# utorch.net
KiCad netlist of a schematic drawn in EAGLE
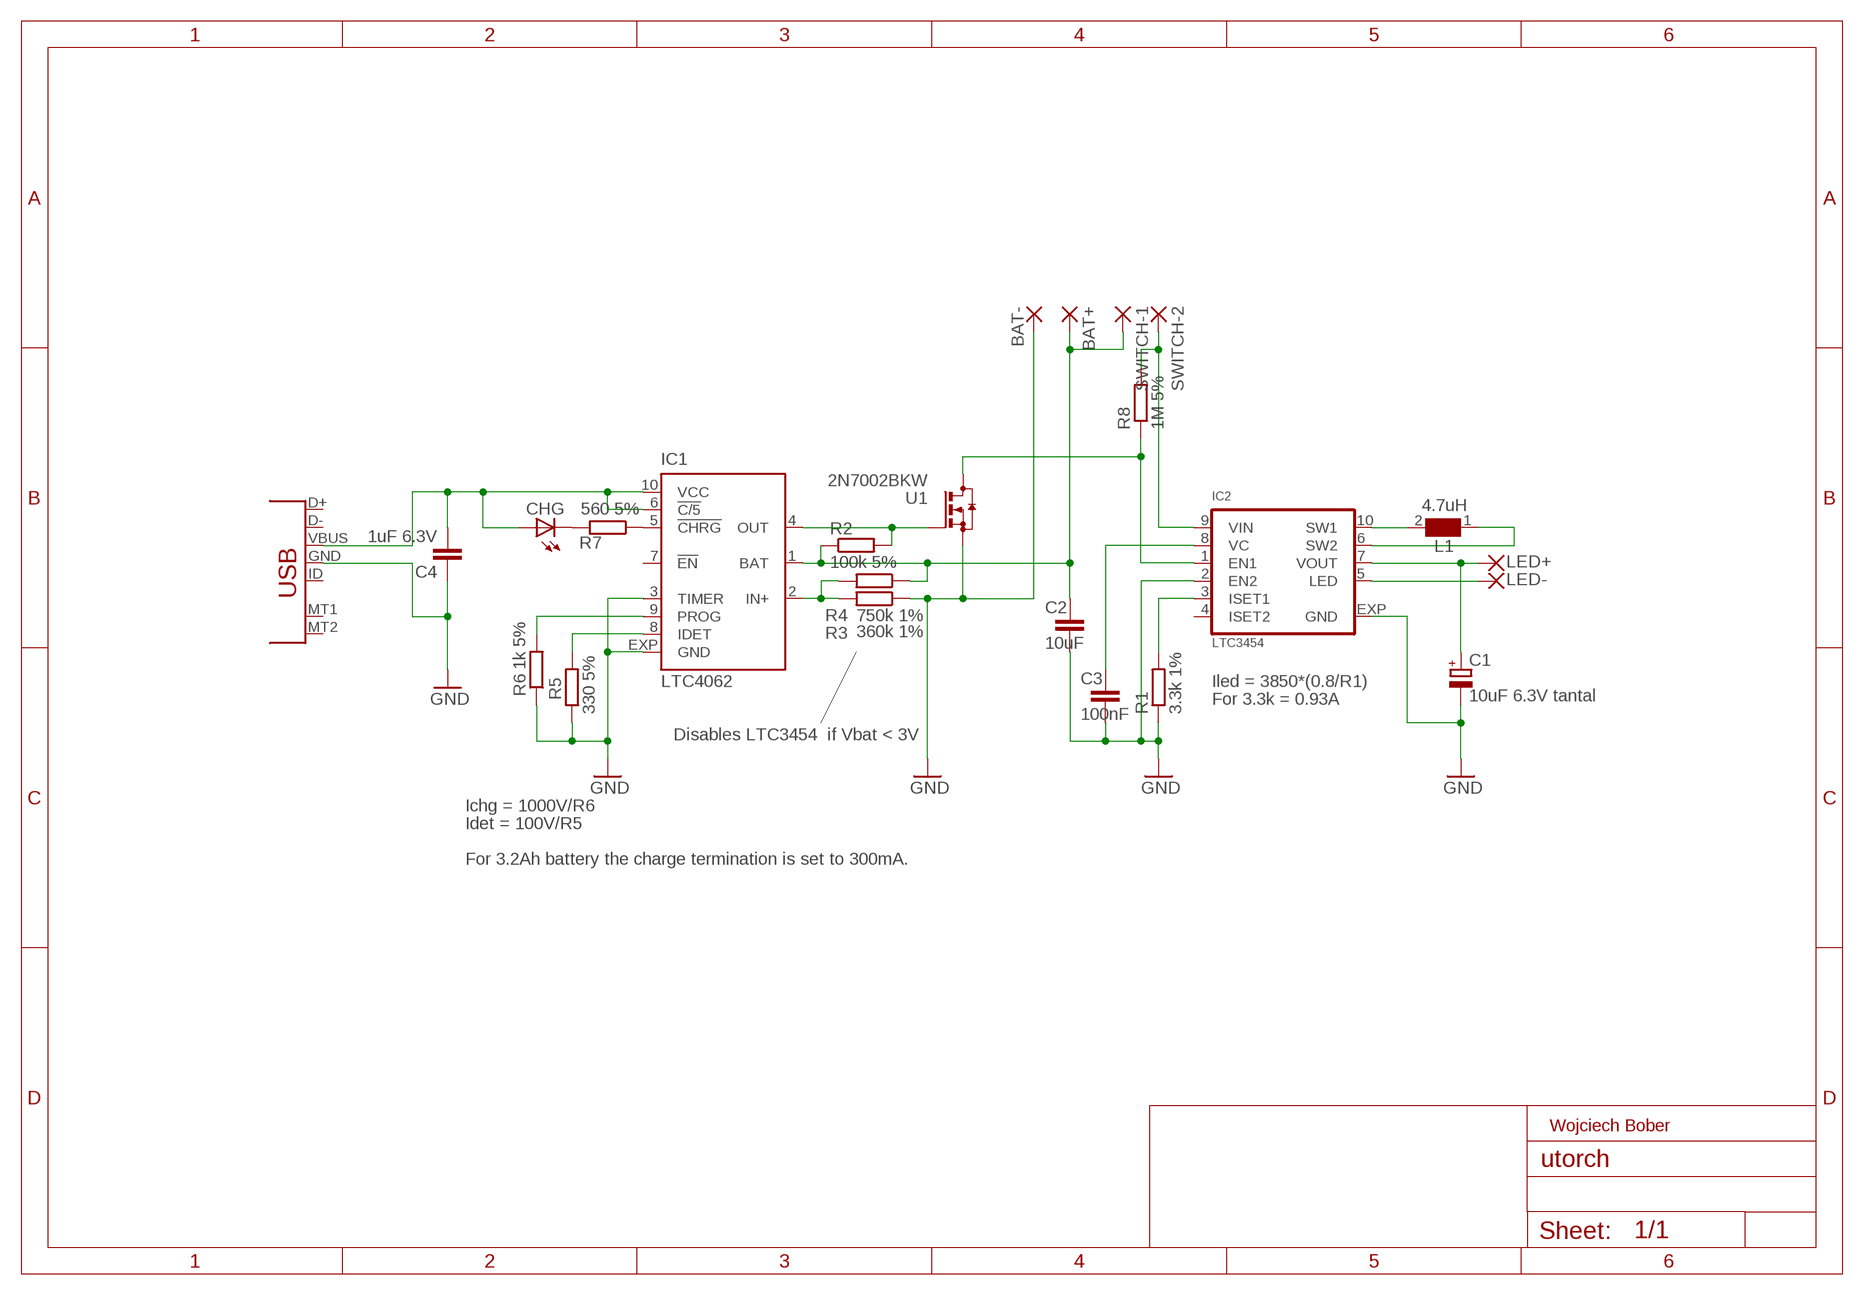
[diagram p0: schematic, sheet 1]

(export (version "E")
  (design (tool "Eeschema 10.0.6"))
  (components
    (comp (ref "BAT+")
      (value "WIREPAD1,6/0,8")
      (footprint "eagle-import:1,6_0,8")
      (libsource (lib "eagle-import") (part "WIREPAD1,6/0,8"))
    )
    (comp (ref "BAT-")
      (value "WIREPAD1,6/0,8")
      (footprint "eagle-import:1,6_0,8")
      (libsource (lib "eagle-import") (part "WIREPAD1,6/0,8"))
    )
    (comp (ref "C1")
      (value "10uF 6.3V tantal")
      (footprint "eagle-import:SMC_A")
      (libsource (lib "eagle-import") (part "CPOL-EUSMCA"))
    )
    (comp (ref "C2")
      (value "10uF")
      (footprint "eagle-import:C0603")
      (libsource (lib "eagle-import") (part "rcl_C-EUC0603"))
    )
    (comp (ref "C3")
      (value "100nF")
      (footprint "eagle-import:ADL_LIB_001_C0402")
      (libsource (lib "eagle-import") (part "C-EUC0402"))
    )
    (comp (ref "C4")
      (value "1uF 6.3V")
      (footprint "eagle-import:ADL_LIB_001_C0402")
      (libsource (lib "eagle-import") (part "C-EUC0402"))
    )
    (comp (ref "CHG")
      (value "LEDCHIP-LED0603")
      (footprint "eagle-import:CHIP-LED0603")
      (libsource (lib "eagle-import") (part "LEDCHIP-LED0603"))
    )
    (comp (ref "IC1")
      (value "LTC4062")
      (footprint "eagle-import:DFN10-3X3")
      (fields (field (name "MPN") "LTC4062EDD#PBF"))
      (libsource (lib "eagle-import") (part "LTC4062"))
    )
    (comp (ref "IC2")
      (value "LTC3454")
      (footprint "eagle-import:DFN10-3X3")
      (libsource (lib "eagle-import") (part "LTC3454"))
    )
    (comp (ref "L1")
      (value "4.7uH")
      (footprint "eagle-import:WE-MAPI_2510")
      (libsource (lib "eagle-import") (part "WE-MAPI2510"))
    )
    (comp (ref "LED+")
      (value "WIREPAD1,6/0,8")
      (footprint "eagle-import:1,6_0,8")
      (libsource (lib "eagle-import") (part "WIREPAD1,6/0,8"))
    )
    (comp (ref "LED-")
      (value "WIREPAD1,6/0,8")
      (footprint "eagle-import:1,6_0,8")
      (libsource (lib "eagle-import") (part "WIREPAD1,6/0,8"))
    )
    (comp (ref "R1")
      (value "3.3k 1%")
      (footprint "eagle-import:ADL_LIB_001_R0402")
      (libsource (lib "eagle-import") (part "R-EU_R0402"))
    )
    (comp (ref "R2")
      (value "100k 5%")
      (footprint "eagle-import:ADL_LIB_001_R0402")
      (libsource (lib "eagle-import") (part "R-EU_R0402"))
    )
    (comp (ref "R3")
      (value "360k 1%")
      (footprint "eagle-import:ADL_LIB_001_R0402")
      (libsource (lib "eagle-import") (part "R-EU_R0402"))
    )
    (comp (ref "R4")
      (value "750k 1%")
      (footprint "eagle-import:ADL_LIB_001_R0402")
      (libsource (lib "eagle-import") (part "R-EU_R0402"))
    )
    (comp (ref "R5")
      (value "330 5%")
      (footprint "eagle-import:R0402")
      (libsource (lib "eagle-import") (part "resistor_R-EU_R0402"))
    )
    (comp (ref "R6")
      (value "1k 5%")
      (footprint "eagle-import:R0402")
      (libsource (lib "eagle-import") (part "resistor_R-EU_R0402"))
    )
    (comp (ref "R7")
      (value "560 5%")
      (footprint "eagle-import:R0402")
      (libsource (lib "eagle-import") (part "resistor_R-EU_R0402"))
    )
    (comp (ref "R8")
      (value "1M 5%")
      (footprint "eagle-import:ADL_LIB_001_R0402")
      (libsource (lib "eagle-import") (part "R-EU_R0402"))
    )
    (comp (ref "SWITCH-1")
      (value "WIREPAD1,6/0,8")
      (footprint "eagle-import:1,6_0,8")
      (libsource (lib "eagle-import") (part "WIREPAD1,6/0,8"))
    )
    (comp (ref "SWITCH-2")
      (value "WIREPAD1,6/0,8")
      (footprint "eagle-import:1,6_0,8")
      (libsource (lib "eagle-import") (part "WIREPAD1,6/0,8"))
    )
    (comp (ref "U1")
      (value "2N7002BKW")
      (footprint "eagle-import:SOT323")
      (libsource (lib "eagle-import") (part "2N7002BKW"))
    )
    (comp (ref "X1")
      (value "USB-MICROB")
      (footprint "eagle-import:USB-MICROB")
      (libsource (lib "eagle-import") (part "USB-MICROB"))
    )
  )
  (nets
    (net (code "1") (name "GND") (class "Default")
      (node (ref "BAT-") (pin "1") (pinfunction "P_1") (pintype "passive"))
      (node (ref "C1") (pin "-") (pinfunction "-_-") (pintype "passive"))
      (node (ref "C2") (pin "2") (pinfunction "2_2") (pintype "passive"))
      (node (ref "C3") (pin "1") (pinfunction "1_1") (pintype "passive"))
      (node (ref "C4") (pin "1") (pinfunction "1_1") (pintype "passive"))
      (node (ref "IC1") (pin "3") (pinfunction "TIMER_3") (pintype "passive"))
      (node (ref "IC1") (pin "EXP") (pinfunction "GND_EXP") (pintype "power_in"))
      (node (ref "IC2") (pin "2") (pinfunction "EN2_2") (pintype "bidirectional"))
      (node (ref "IC2") (pin "EXP") (pinfunction "GND_EXP") (pintype "bidirectional"))
      (node (ref "R1") (pin "1") (pinfunction "1_1") (pintype "passive"))
      (node (ref "R3") (pin "1") (pinfunction "1_1") (pintype "passive"))
      (node (ref "R5") (pin "1") (pinfunction "1_1") (pintype "passive"))
      (node (ref "R6") (pin "1") (pinfunction "1_1") (pintype "passive"))
      (node (ref "U1") (pin "2") (pinfunction "S_2") (pintype "passive"))
      (node (ref "X1") (pin "GND") (pinfunction "GND_GND") (pintype "bidirectional"))
    )
    (net (code "2") (name "Net-(BAT+-P)") (class "Default")
      (node (ref "BAT+") (pin "1") (pinfunction "P_1") (pintype "passive"))
      (node (ref "C2") (pin "1") (pinfunction "1_1") (pintype "passive"))
      (node (ref "IC1") (pin "1") (pinfunction "BAT_1") (pintype "passive"))
      (node (ref "R2") (pin "1") (pinfunction "1_1") (pintype "passive"))
      (node (ref "R4") (pin "1") (pinfunction "1_1") (pintype "passive"))
      (node (ref "SWITCH-1") (pin "1") (pinfunction "P_1") (pintype "passive"))
    )
    (net (code "3") (name "Net-(CHG-PadC)") (class "Default")
      (node (ref "CHG") (pin "C") (pinfunction "C_C") (pintype "passive"))
      (node (ref "R7") (pin "2") (pinfunction "2_2") (pintype "passive"))
    )
    (net (code "4") (name "Net-(IC1-IDET)") (class "Default")
      (node (ref "IC1") (pin "8") (pinfunction "IDET_8") (pintype "passive"))
      (node (ref "R5") (pin "2") (pinfunction "2_2") (pintype "passive"))
    )
    (net (code "5") (name "Net-(IC1-IN+)") (class "Default")
      (node (ref "IC1") (pin "2") (pinfunction "IN+_2") (pintype "input"))
      (node (ref "R3") (pin "2") (pinfunction "2_2") (pintype "passive"))
      (node (ref "R4") (pin "2") (pinfunction "2_2") (pintype "passive"))
    )
    (net (code "6") (name "Net-(IC1-OUT)") (class "Default")
      (node (ref "IC1") (pin "4") (pinfunction "OUT_4") (pintype "open_collector"))
      (node (ref "R2") (pin "2") (pinfunction "2_2") (pintype "passive"))
      (node (ref "U1") (pin "1") (pinfunction "G_1") (pintype "passive"))
    )
    (net (code "7") (name "Net-(IC1-PROG)") (class "Default")
      (node (ref "IC1") (pin "9") (pinfunction "PROG_9") (pintype "passive"))
      (node (ref "R6") (pin "2") (pinfunction "2_2") (pintype "passive"))
    )
    (net (code "8") (name "Net-(IC1-VCC)") (class "Default")
      (node (ref "C4") (pin "2") (pinfunction "2_2") (pintype "passive"))
      (node (ref "CHG") (pin "A") (pinfunction "A_A") (pintype "passive"))
      (node (ref "IC1") (pin "10") (pinfunction "VCC_10") (pintype "power_in"))
      (node (ref "IC1") (pin "6") (pinfunction "~{C/5}_6") (pintype "input"))
      (node (ref "X1") (pin "VBUS") (pinfunction "VBUS_VBUS") (pintype "bidirectional"))
    )
    (net (code "9") (name "Net-(IC1-~{CHRG})") (class "Default")
      (node (ref "IC1") (pin "5") (pinfunction "~{CHRG}_5") (pintype "open_collector"))
      (node (ref "R7") (pin "1") (pinfunction "1_1") (pintype "passive"))
    )
    (net (code "10") (name "Net-(IC2-EN1)") (class "Default")
      (node (ref "IC2") (pin "1") (pinfunction "EN1_1") (pintype "bidirectional"))
      (node (ref "R8") (pin "1") (pinfunction "1_1") (pintype "passive"))
      (node (ref "U1") (pin "3") (pinfunction "D_3") (pintype "passive"))
    )
    (net (code "11") (name "Net-(IC2-ISET1)") (class "Default")
      (node (ref "IC2") (pin "3") (pinfunction "ISET1_3") (pintype "bidirectional"))
      (node (ref "R1") (pin "2") (pinfunction "2_2") (pintype "passive"))
    )
    (net (code "12") (name "Net-(IC2-LED)") (class "Default")
      (node (ref "IC2") (pin "5") (pinfunction "LED_5") (pintype "bidirectional"))
      (node (ref "LED-") (pin "1") (pinfunction "P_1") (pintype "passive"))
    )
    (net (code "13") (name "Net-(IC2-SW1)") (class "Default")
      (node (ref "IC2") (pin "10") (pinfunction "SW1_10") (pintype "bidirectional"))
      (node (ref "L1") (pin "2") (pinfunction "2_2") (pintype "passive"))
    )
    (net (code "14") (name "Net-(IC2-SW2)") (class "Default")
      (node (ref "IC2") (pin "6") (pinfunction "SW2_6") (pintype "bidirectional"))
      (node (ref "L1") (pin "1") (pinfunction "1_1") (pintype "passive"))
    )
    (net (code "15") (name "Net-(IC2-VC)") (class "Default")
      (node (ref "C3") (pin "2") (pinfunction "2_2") (pintype "passive"))
      (node (ref "IC2") (pin "8") (pinfunction "VC_8") (pintype "bidirectional"))
    )
    (net (code "16") (name "Net-(IC2-VIN)") (class "Default")
      (node (ref "IC2") (pin "9") (pinfunction "VIN_9") (pintype "bidirectional"))
      (node (ref "R8") (pin "2") (pinfunction "2_2") (pintype "passive"))
      (node (ref "SWITCH-2") (pin "1") (pinfunction "P_1") (pintype "passive"))
    )
    (net (code "17") (name "Net-(IC2-VOUT)") (class "Default")
      (node (ref "C1") (pin "+") (pinfunction "+_+") (pintype "passive"))
      (node (ref "IC2") (pin "7") (pinfunction "VOUT_7") (pintype "bidirectional"))
      (node (ref "LED+") (pin "1") (pinfunction "P_1") (pintype "passive"))
    )
    (net (code "18") (name "unconnected-(IC1-~{EN}-Pad7)") (class "Default")
      (node (ref "IC1") (pin "7") (pinfunction "~{EN}_7") (pintype "input"))
    )
    (net (code "19") (name "unconnected-(IC2-ISET2-Pad4)") (class "Default")
      (node (ref "IC2") (pin "4") (pinfunction "ISET2_4") (pintype "bidirectional"))
    )
    (net (code "20") (name "unconnected-(X1-PadD+)") (class "Default")
      (node (ref "X1") (pin "D+") (pinfunction "D+_D+") (pintype "bidirectional"))
    )
    (net (code "21") (name "unconnected-(X1-PadD-)") (class "Default")
      (node (ref "X1") (pin "D-") (pinfunction "D-_D-") (pintype "bidirectional"))
    )
    (net (code "22") (name "unconnected-(X1-PadID)") (class "Default")
      (node (ref "X1") (pin "ID") (pinfunction "ID_ID") (pintype "bidirectional"))
    )
    (net (code "23") (name "unconnected-(X1-PadMT1)") (class "Default")
      (node (ref "X1") (pin "MT1") (pinfunction "MT1_MT1") (pintype "bidirectional"))
    )
    (net (code "24") (name "unconnected-(X1-PadMT2)") (class "Default")
      (node (ref "X1") (pin "MT2") (pinfunction "MT2_MT2") (pintype "bidirectional"))
    )
  )
)
